# 4c_-_Latching_BSPD.net
KiCad netlist of a schematic drawn in Altium Designer
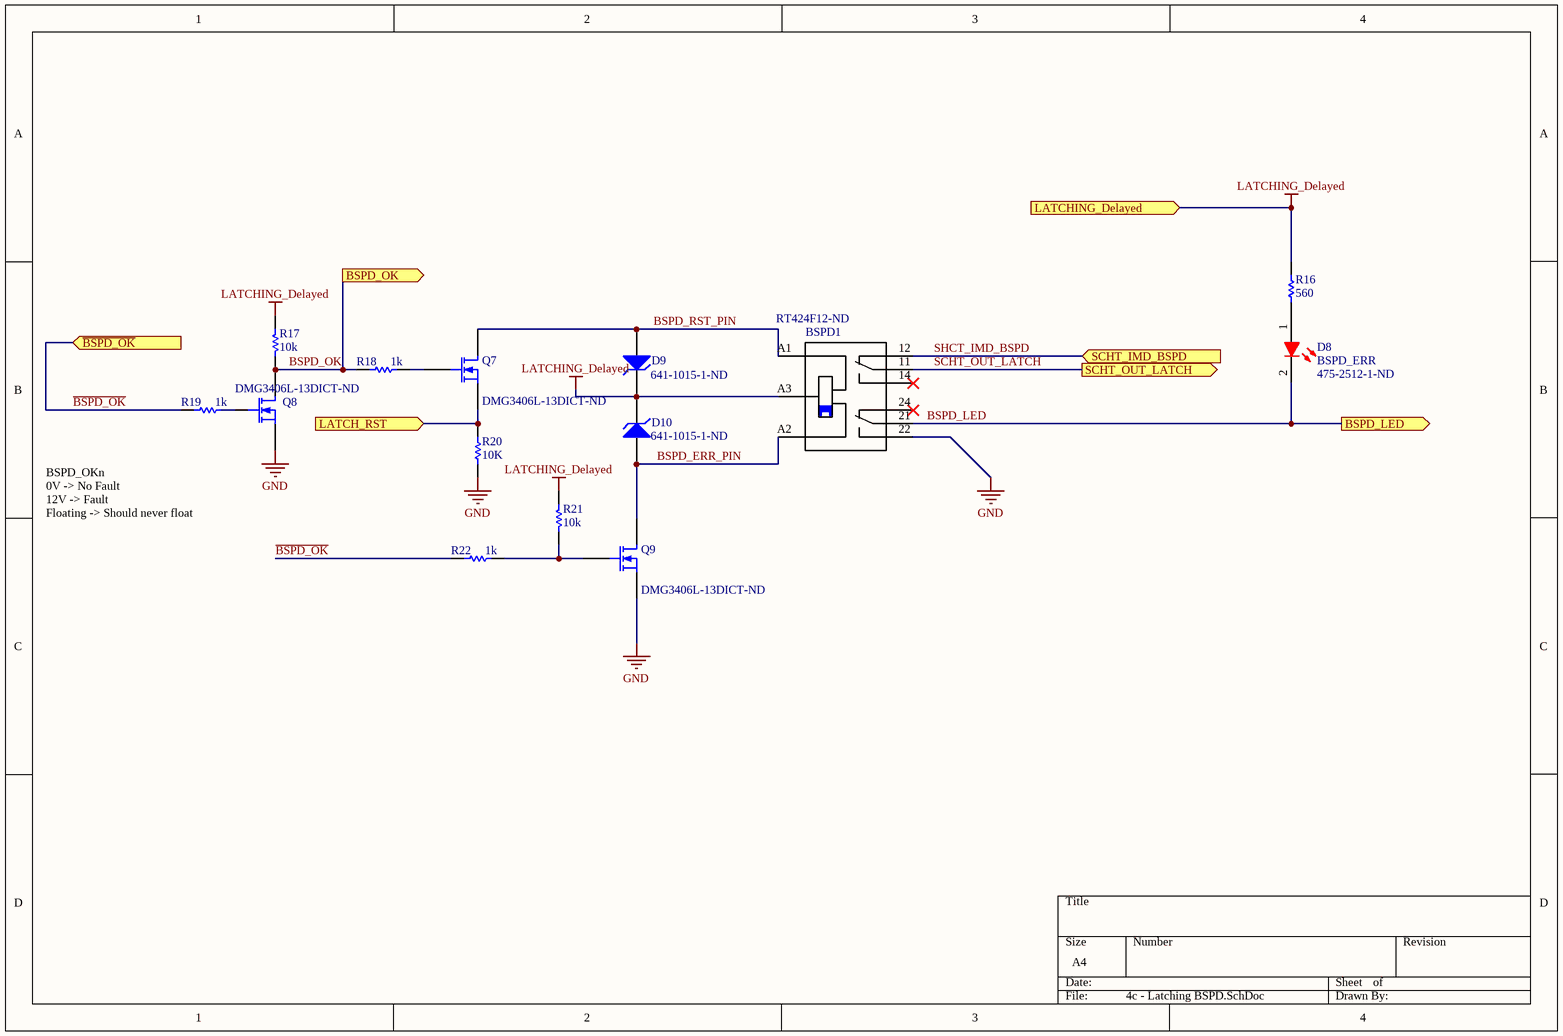
[diagram p0: 4c - Latching BSPD.SchDoc]

(export (version "E")
  (design (tool "Eeschema 10.0.6"))
  (components
    (comp (ref "BSPD1")
      (value "5-1393243-4")
      (footprint "TE_5-1393243-4")
      (description "Electromechanical Relay 12VDC 240Ohm 15A DPDT __ 29mm 12.7mm 15.7mm__ THT Power Relay")
      (fields (field (name "MF") "TE Connectivity") (field (name "SUPPLIER PART NUMBER 1") "RT424F12-ND"))
      (libsource (lib "5-1393243-4") (part "5-1393243-4"))
    )
    (comp (ref "D8")
      (value "BSPD_ERR")
      (footprint "TOSH-0603LED_RED_V")
      (description "LED, Red 0603 (1608) 63mCd")
      (fields
        (field (name "MANUFACTURER") "Toshiba")
        (field (name "PARTNUMBER") "TLSU1008A(T04)")
        (field (name "SUPPLIER PART NUMBER 1") "475-2512-1-ND")
      )
      (libsource (lib "Altium Content Vault") (part "CMP-0444-00001-1"))
    )
    (comp (ref "D9")
      (value "D Zener")
      (footprint "DO214AC")
      (description "Zener Diode")
      (fields
        (field (name "SUPPLIER PART NUMBER 1") "641-1015-1-ND")
        (field (name "PUBLISHER") "Altium Limited")
      )
      (libsource (lib "Miscellaneous Devices") (part "D Zener"))
    )
    (comp (ref "D10")
      (value "D Zener")
      (footprint "DO214AC")
      (description "Zener Diode")
      (fields
        (field (name "SUPPLIER PART NUMBER 1") "641-1015-1-ND")
        (field (name "PUBLISHER") "Altium Limited")
      )
      (libsource (lib "Miscellaneous Devices") (part "D Zener"))
    )
    (comp (ref "Q7")
      (value "~")
      (footprint "SOT-23_N")
      (description "N-Channel MOSFET")
      (fields
        (field (name "MANUFACTURER") "Infineon Technologies")
        (field (name "SUPPLIER PART NUMBER 1") "DMG3406L-13DICT-ND")
        (field (name "PUBLISHER") "Altium Limited")
      )
      (libsource (lib "Miscellaneous Devices") (part "MOSFET-N"))
    )
    (comp (ref "Q8")
      (value "~")
      (footprint "SOT-23_N")
      (description "N-Channel MOSFET")
      (fields
        (field (name "MANUFACTURER") "Infineon Technologies")
        (field (name "SUPPLIER PART NUMBER 1") "DMG3406L-13DICT-ND")
        (field (name "PUBLISHER") "Altium Limited")
      )
      (libsource (lib "Miscellaneous Devices") (part "MOSFET-N"))
    )
    (comp (ref "Q9")
      (value "~")
      (footprint "SOT-23_N")
      (description "N-Channel MOSFET")
      (fields
        (field (name "MANUFACTURER") "Infineon Technologies")
        (field (name "SUPPLIER PART NUMBER 1") "DMG3406L-13DICT-ND")
        (field (name "PUBLISHER") "Altium Limited")
      )
      (libsource (lib "Miscellaneous Devices") (part "MOSFET-N"))
    )
    (comp (ref "R16")
      (value "560")
      (footprint "RESC0603(1608)_L")
      (description "0603 (1608 Metric) Chip Resistor")
      (libsource (lib "Altium Content Vault") (part "RES_3"))
    )
    (comp (ref "R17")
      (value "RHM1.0KDCT-ND")
      (footprint "1608[0603]")
      (description "RES SMD 1.0K OHM 5% 1/4W 0603")
      (fields
        (field (name "MANUFACTURER") "Rohm Semiconductor")
        (field (name "MANUFACTURER PART NUMBER") "ESR03EZPJ102")
        (field (name "RESISTANCE (OHMS)") "10k")
      )
      (libsource (lib "Miscellaneous Devices") (part "Res1"))
    )
    (comp (ref "R18")
      (value "1k")
      (footprint "1608[0603]")
      (description "RES SMD 100 OHM 5% 1/4W 0603")
      (fields
        (field (name "MANUFACTURER") "Rohm Semiconductor")
        (field (name "MANUFACTURER PART NUMBER") "ESR03EZPJ101")
        (field (name "PUBLISHER") "Altium Limited")
      )
      (libsource (lib "Miscellaneous Devices") (part "Res1"))
    )
    (comp (ref "R19")
      (value "1k")
      (footprint "1608[0603]")
      (description "RES SMD 100 OHM 5% 1/4W 0603")
      (fields
        (field (name "MANUFACTURER") "Rohm Semiconductor")
        (field (name "MANUFACTURER PART NUMBER") "ESR03EZPJ101")
        (field (name "PUBLISHER") "Altium Limited")
      )
      (libsource (lib "Miscellaneous Devices") (part "Res1"))
    )
    (comp (ref "R20")
      (value "10K")
      (footprint "1608[0603]")
      (description "RES SMD 10K OHM 5% 1/4W 0603")
      (fields
        (field (name "MANUFACTURER") "Rohm Semiconductor")
        (field (name "MANUFACTURER PART NUMBER") "ESR03EZPJ103")
        (field (name "PUBLISHER") "Altium Limited")
      )
      (libsource (lib "Miscellaneous Devices") (part "Res1"))
    )
    (comp (ref "R21")
      (value "RHM1.0KDCT-ND")
      (footprint "1608[0603]")
      (description "RES SMD 1.0K OHM 5% 1/4W 0603")
      (fields
        (field (name "MANUFACTURER") "Rohm Semiconductor")
        (field (name "MANUFACTURER PART NUMBER") "ESR03EZPJ102")
        (field (name "RESISTANCE (OHMS)") "10k")
      )
      (libsource (lib "Miscellaneous Devices") (part "Res1"))
    )
    (comp (ref "R22")
      (value "1k")
      (footprint "1608[0603]")
      (description "RES SMD 100 OHM 5% 1/4W 0603")
      (fields
        (field (name "MANUFACTURER") "Rohm Semiconductor")
        (field (name "MANUFACTURER PART NUMBER") "ESR03EZPJ101")
        (field (name "PUBLISHER") "Altium Limited")
      )
      (libsource (lib "Miscellaneous Devices") (part "Res1"))
    )
  )
  (nets
    (net (code "1") (name "/BSPD_ERR_PIN") (class "Default")
      (node (ref "BSPD1") (pin "A2") (pinfunction "A2_A2") (pintype "passive"))
      (node (ref "D10") (pin "1") (pinfunction "A_1") (pintype "passive"))
      (node (ref "Q9") (pin "3") (pinfunction "D_3") (pintype "passive"))
    )
    (net (code "2") (name "/BSPD_LED") (class "Default")
      (node (ref "BSPD1") (pin "21") (pinfunction "21_21") (pintype "passive"))
      (node (ref "D8") (pin "2") (pinfunction "K_2") (pintype "passive"))
    )
    (net (code "3") (name "/BSPD_OK") (class "Default")
      (node (ref "Q8") (pin "3") (pinfunction "D_3") (pintype "passive"))
      (node (ref "R17") (pin "2") (pinfunction "2_2") (pintype "passive"))
      (node (ref "R18") (pin "1") (pinfunction "1_1") (pintype "passive"))
    )
    (net (code "4") (name "/BSPD_RST_PIN") (class "Default")
      (node (ref "BSPD1") (pin "A1") (pinfunction "A1_A1") (pintype "passive"))
      (node (ref "D9") (pin "1") (pinfunction "A_1") (pintype "passive"))
      (node (ref "Q7") (pin "3") (pinfunction "D_3") (pintype "passive"))
    )
    (net (code "5") (name "/LATCH_RST") (class "Default")
      (node (ref "Q7") (pin "2") (pinfunction "S_2") (pintype "passive"))
      (node (ref "R20") (pin "2") (pinfunction "2_2") (pintype "passive"))
    )
    (net (code "6") (name "/SCHT_OUT_LATCH") (class "Default")
      (node (ref "BSPD1") (pin "11") (pinfunction "11_11") (pintype "passive"))
    )
    (net (code "7") (name "/SHCT_IMD_BSPD") (class "Default")
      (node (ref "BSPD1") (pin "12") (pinfunction "12_12") (pintype "passive"))
    )
    (net (code "8") (name "/~{BSPD_OK}") (class "Default")
      (node (ref "R19") (pin "1") (pinfunction "1_1") (pintype "passive"))
      (node (ref "R22") (pin "1") (pinfunction "1_1") (pintype "passive"))
    )
    (net (code "9") (name "GND") (class "Default")
      (node (ref "BSPD1") (pin "22") (pinfunction "22_22") (pintype "passive"))
      (node (ref "Q8") (pin "2") (pinfunction "S_2") (pintype "passive"))
      (node (ref "Q9") (pin "2") (pinfunction "S_2") (pintype "passive"))
      (node (ref "R20") (pin "1") (pinfunction "1_1") (pintype "passive"))
    )
    (net (code "10") (name "LATCHING_Delayed") (class "Default")
      (node (ref "BSPD1") (pin "A3") (pinfunction "A3_A3") (pintype "passive"))
      (node (ref "D10") (pin "2") (pinfunction "K_2") (pintype "passive"))
      (node (ref "D9") (pin "2") (pinfunction "K_2") (pintype "passive"))
      (node (ref "R16") (pin "2") (pinfunction "2_2") (pintype "passive"))
      (node (ref "R17") (pin "1") (pinfunction "1_1") (pintype "passive"))
      (node (ref "R21") (pin "1") (pinfunction "1_1") (pintype "passive"))
    )
    (net (code "11") (name "Net-(D8-A)") (class "Default")
      (node (ref "D8") (pin "1") (pinfunction "A_1") (pintype "passive"))
      (node (ref "R16") (pin "1") (pinfunction "1_1") (pintype "passive"))
    )
    (net (code "12") (name "Net-(Q7-G)") (class "Default")
      (node (ref "Q7") (pin "1") (pinfunction "G_1") (pintype "passive"))
      (node (ref "R18") (pin "2") (pinfunction "2_2") (pintype "passive"))
    )
    (net (code "13") (name "Net-(Q8-G)") (class "Default")
      (node (ref "Q8") (pin "1") (pinfunction "G_1") (pintype "passive"))
      (node (ref "R19") (pin "2") (pinfunction "2_2") (pintype "passive"))
    )
    (net (code "14") (name "Net-(Q9-G)") (class "Default")
      (node (ref "Q9") (pin "1") (pinfunction "G_1") (pintype "passive"))
      (node (ref "R21") (pin "2") (pinfunction "2_2") (pintype "passive"))
      (node (ref "R22") (pin "2") (pinfunction "2_2") (pintype "passive"))
    )
    (net (code "15") (name "unconnected-(BSPD1-Pad14)") (class "Default")
      (node (ref "BSPD1") (pin "14") (pinfunction "14_14") (pintype "passive+no_connect"))
    )
    (net (code "16") (name "unconnected-(BSPD1-Pad24)") (class "Default")
      (node (ref "BSPD1") (pin "24") (pinfunction "24_24") (pintype "passive+no_connect"))
    )
  )
)
